# ICE.net
KiCad netlist of a schematic drawn in Altium Designer
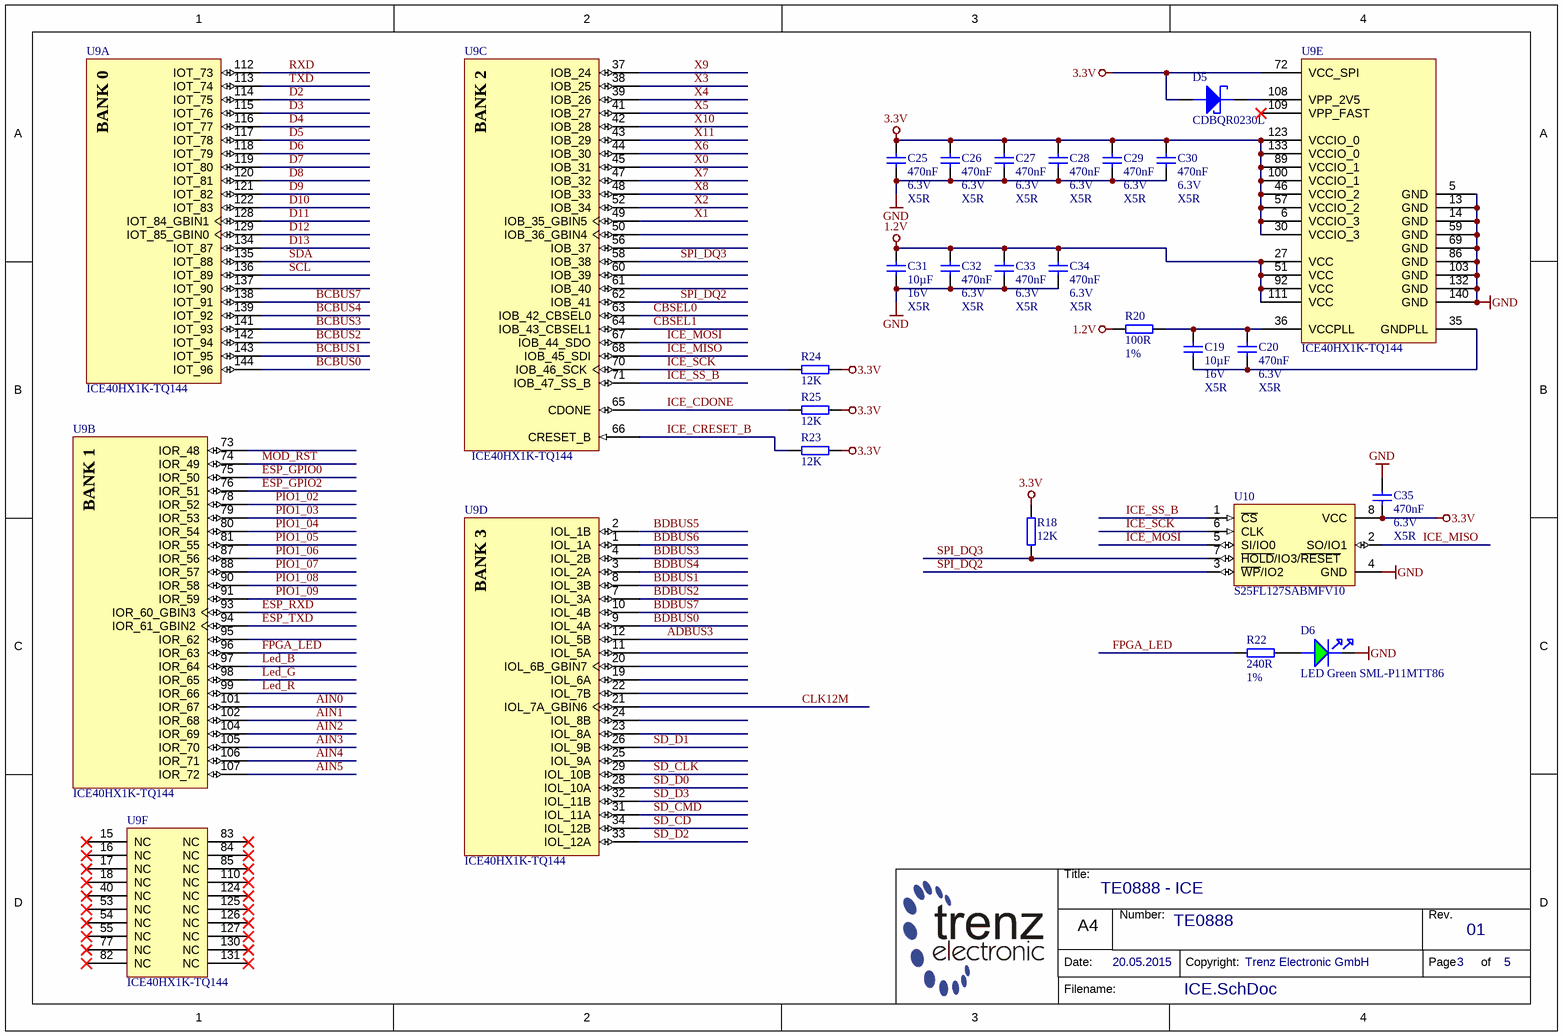
[diagram p0: ICE.SchDoc]

(export (version "E")
  (design (tool "Eeschema 10.0.6"))
  (components
    (comp (ref "C19")
      (value "10µF")
      (footprint "CAPC1608X90N")
      (description "KON 10µF 16V X5R SMD 20%")
      (fields
        (field (name "VOLTAGE") "16V")
        (field (name "TECHNOLOGY") "X5R")
        (field (name "TOLERANCE") "20%")
      )
      (libsource (lib "TE") (part "CAP-NP"))
    )
    (comp (ref "C20")
      (value "470nF")
      (footprint "CAPC0603X33N")
      (description "KON 470nF X5R 6.3V SMD 20%")
      (fields
        (field (name "VOLTAGE") "6.3V")
        (field (name "TECHNOLOGY") "X5R")
        (field (name "TOLERANCE") "20%")
      )
      (libsource (lib "TE") (part "CAP-NP"))
    )
    (comp (ref "C25")
      (value "470nF")
      (footprint "CAPC0603X33N")
      (description "KON 470nF X5R 6.3V SMD 20%")
      (fields
        (field (name "VOLTAGE") "6.3V")
        (field (name "TECHNOLOGY") "X5R")
        (field (name "TOLERANCE") "20%")
      )
      (libsource (lib "TE") (part "CAP-NP"))
    )
    (comp (ref "C26")
      (value "470nF")
      (footprint "CAPC0603X33N")
      (description "KON 470nF X5R 6.3V SMD 20%")
      (fields
        (field (name "VOLTAGE") "6.3V")
        (field (name "TECHNOLOGY") "X5R")
        (field (name "TOLERANCE") "20%")
      )
      (libsource (lib "TE") (part "CAP-NP"))
    )
    (comp (ref "C27")
      (value "470nF")
      (footprint "CAPC0603X33N")
      (description "KON 470nF X5R 6.3V SMD 20%")
      (fields
        (field (name "VOLTAGE") "6.3V")
        (field (name "TECHNOLOGY") "X5R")
        (field (name "TOLERANCE") "20%")
      )
      (libsource (lib "TE") (part "CAP-NP"))
    )
    (comp (ref "C28")
      (value "470nF")
      (footprint "CAPC0603X33N")
      (description "KON 470nF X5R 6.3V SMD 20%")
      (fields
        (field (name "VOLTAGE") "6.3V")
        (field (name "TECHNOLOGY") "X5R")
        (field (name "TOLERANCE") "20%")
      )
      (libsource (lib "TE") (part "CAP-NP"))
    )
    (comp (ref "C29")
      (value "470nF")
      (footprint "CAPC0603X33N")
      (description "KON 470nF X5R 6.3V SMD 20%")
      (fields
        (field (name "VOLTAGE") "6.3V")
        (field (name "TECHNOLOGY") "X5R")
        (field (name "TOLERANCE") "20%")
      )
      (libsource (lib "TE") (part "CAP-NP"))
    )
    (comp (ref "C30")
      (value "470nF")
      (footprint "CAPC0603X33N")
      (description "KON 470nF X5R 6.3V SMD 20%")
      (fields
        (field (name "VOLTAGE") "6.3V")
        (field (name "TECHNOLOGY") "X5R")
        (field (name "TOLERANCE") "20%")
      )
      (libsource (lib "TE") (part "CAP-NP"))
    )
    (comp (ref "C31")
      (value "10µF")
      (footprint "CAPC1608X90N")
      (description "KON 10µF 16V X5R SMD 20%")
      (fields
        (field (name "VOLTAGE") "16V")
        (field (name "TECHNOLOGY") "X5R")
        (field (name "TOLERANCE") "20%")
      )
      (libsource (lib "TE") (part "CAP-NP"))
    )
    (comp (ref "C32")
      (value "470nF")
      (footprint "CAPC0603X33N")
      (description "KON 470nF X5R 6.3V SMD 20%")
      (fields
        (field (name "VOLTAGE") "6.3V")
        (field (name "TECHNOLOGY") "X5R")
        (field (name "TOLERANCE") "20%")
      )
      (libsource (lib "TE") (part "CAP-NP"))
    )
    (comp (ref "C33")
      (value "470nF")
      (footprint "CAPC0603X33N")
      (description "KON 470nF X5R 6.3V SMD 20%")
      (fields
        (field (name "VOLTAGE") "6.3V")
        (field (name "TECHNOLOGY") "X5R")
        (field (name "TOLERANCE") "20%")
      )
      (libsource (lib "TE") (part "CAP-NP"))
    )
    (comp (ref "C34")
      (value "470nF")
      (footprint "CAPC0603X33N")
      (description "KON 470nF X5R 6.3V SMD 20%")
      (fields
        (field (name "VOLTAGE") "6.3V")
        (field (name "TECHNOLOGY") "X5R")
        (field (name "TOLERANCE") "20%")
      )
      (libsource (lib "TE") (part "CAP-NP"))
    )
    (comp (ref "C35")
      (value "470nF")
      (footprint "CAPC0603X33N")
      (description "KON 470nF X5R 6.3V SMD 20%")
      (fields
        (field (name "VOLTAGE") "6.3V")
        (field (name "TECHNOLOGY") "X5R")
        (field (name "TOLERANCE") "20%")
      )
      (libsource (lib "TE") (part "CAP-NP"))
    )
    (comp (ref "D5")
      (value "CDBQR0230L")
      (footprint "DIOC1006X55N")
      (fields (field (name "VOLTAGE") "0.2A"))
      (libsource (lib "TE") (part "SCHOTTKY"))
    )
    (comp (ref "D6")
      (value "LED Green SML-P11MTT86")
      (footprint "LEDC1006X25N_GREEN")
      (description "LED Grün SML-P11MTT86 SMD")
      (libsource (lib "TE") (part "LED_GRUEN"))
    )
    (comp (ref "R18")
      (value "12K")
      (footprint "RESC1005X40N")
      (description "WID SMD 12K 1% 0,063W")
      (libsource (lib "TE") (part "RES"))
    )
    (comp (ref "R20")
      (value "100R")
      (footprint "RESC1005X40N")
      (description "WID SMD 100R 1% 0,063W")
      (fields (field (name "TOLERANCE") "1%"))
      (libsource (lib "TE") (part "RES"))
    )
    (comp (ref "R22")
      (value "240R")
      (footprint "RESC1005X40N")
      (description "WID SMD 240R 1% 0,063W")
      (fields (field (name "TOLERANCE") "1%"))
      (libsource (lib "TE") (part "RES"))
    )
    (comp (ref "R23")
      (value "12K")
      (footprint "RESC1005X40N")
      (description "WID SMD 12K 1% 0,063W")
      (libsource (lib "TE") (part "RES"))
    )
    (comp (ref "R24")
      (value "12K")
      (footprint "RESC1005X40N")
      (description "WID SMD 12K 1% 0,063W")
      (libsource (lib "TE") (part "RES"))
    )
    (comp (ref "R25")
      (value "12K")
      (footprint "RESC1005X40N")
      (description "WID SMD 12K 1% 0,063W")
      (libsource (lib "TE") (part "RES"))
    )
    (comp (ref "U9")
      (value "ICE40HX1K-TQ144")
      (footprint "LATC-TQFP-144_N")
      (fields (field (name "MANUFACTURER") "Lattice Semiconductor"))
      (libsource (lib "Lattice iCE40") (part "ICE40HX1K-TQ144"))
    )
    (comp (ref "U10")
      (value "S25FL127SABMFV10")
      (footprint "SOIC127P790X216-8N")
      (description "S25FL127SABMFV10 automotive SO8")
      (libsource (lib "TE") (part "S25FL127S-SO8"))
    )
  )
  (nets
    (net (code "1") (name "/ADBUS3") (class "Default")
      (node (ref "U9") (pin "12") (pinfunction "IOL_5B_12") (pintype "bidirectional"))
    )
    (net (code "2") (name "/AIN0") (class "Default")
      (node (ref "U9") (pin "101") (pinfunction "IOR_67_101") (pintype "bidirectional"))
    )
    (net (code "3") (name "/AIN1") (class "Default")
      (node (ref "U9") (pin "102") (pinfunction "IOR_68_102") (pintype "bidirectional"))
    )
    (net (code "4") (name "/AIN2") (class "Default")
      (node (ref "U9") (pin "104") (pinfunction "IOR_69_104") (pintype "bidirectional"))
    )
    (net (code "5") (name "/AIN3") (class "Default")
      (node (ref "U9") (pin "105") (pinfunction "IOR_70_105") (pintype "bidirectional"))
    )
    (net (code "6") (name "/AIN4") (class "Default")
      (node (ref "U9") (pin "106") (pinfunction "IOR_71_106") (pintype "bidirectional"))
    )
    (net (code "7") (name "/AIN5") (class "Default")
      (node (ref "U9") (pin "107") (pinfunction "IOR_72_107") (pintype "bidirectional"))
    )
    (net (code "8") (name "/BCBUS0") (class "Default")
      (node (ref "U9") (pin "144") (pinfunction "IOT_96_144") (pintype "bidirectional"))
    )
    (net (code "9") (name "/BCBUS1") (class "Default")
      (node (ref "U9") (pin "143") (pinfunction "IOT_95_143") (pintype "bidirectional"))
    )
    (net (code "10") (name "/BCBUS2") (class "Default")
      (node (ref "U9") (pin "142") (pinfunction "IOT_94_142") (pintype "bidirectional"))
    )
    (net (code "11") (name "/BCBUS3") (class "Default")
      (node (ref "U9") (pin "141") (pinfunction "IOT_93_141") (pintype "bidirectional"))
    )
    (net (code "12") (name "/BCBUS4") (class "Default")
      (node (ref "U9") (pin "139") (pinfunction "IOT_92_139") (pintype "bidirectional"))
    )
    (net (code "13") (name "/BCBUS7") (class "Default")
      (node (ref "U9") (pin "138") (pinfunction "IOT_91_138") (pintype "bidirectional"))
    )
    (net (code "14") (name "/BDBUS0") (class "Default")
      (node (ref "U9") (pin "9") (pinfunction "IOL_4A_9") (pintype "bidirectional"))
    )
    (net (code "15") (name "/BDBUS1") (class "Default")
      (node (ref "U9") (pin "8") (pinfunction "IOL_3B_8") (pintype "bidirectional"))
    )
    (net (code "16") (name "/BDBUS2") (class "Default")
      (node (ref "U9") (pin "7") (pinfunction "IOL_3A_7") (pintype "bidirectional"))
    )
    (net (code "17") (name "/BDBUS3") (class "Default")
      (node (ref "U9") (pin "4") (pinfunction "IOL_2B_4") (pintype "bidirectional"))
    )
    (net (code "18") (name "/BDBUS4") (class "Default")
      (node (ref "U9") (pin "3") (pinfunction "IOL_2A_3") (pintype "bidirectional"))
    )
    (net (code "19") (name "/BDBUS5") (class "Default")
      (node (ref "U9") (pin "2") (pinfunction "IOL_1B_2") (pintype "bidirectional"))
    )
    (net (code "20") (name "/BDBUS6") (class "Default")
      (node (ref "U9") (pin "1") (pinfunction "IOL_1A_1") (pintype "bidirectional"))
    )
    (net (code "21") (name "/BDBUS7") (class "Default")
      (node (ref "U9") (pin "10") (pinfunction "IOL_4B_10") (pintype "bidirectional"))
    )
    (net (code "22") (name "/CBSEL0") (class "Default")
      (node (ref "U9") (pin "63") (pinfunction "IOB_42_CBSEL0_63") (pintype "bidirectional"))
    )
    (net (code "23") (name "/CBSEL1") (class "Default")
      (node (ref "U9") (pin "64") (pinfunction "IOB_43_CBSEL1_64") (pintype "bidirectional"))
    )
    (net (code "24") (name "/CLK12M") (class "Default")
      (node (ref "U9") (pin "21") (pinfunction "IOL_7A_GBIN6_21") (pintype "bidirectional"))
    )
    (net (code "25") (name "/D2") (class "Default")
      (node (ref "U9") (pin "114") (pinfunction "IOT_75_114") (pintype "bidirectional"))
    )
    (net (code "26") (name "/D3") (class "Default")
      (node (ref "U9") (pin "115") (pinfunction "IOT_76_115") (pintype "bidirectional"))
    )
    (net (code "27") (name "/D4") (class "Default")
      (node (ref "U9") (pin "116") (pinfunction "IOT_77_116") (pintype "bidirectional"))
    )
    (net (code "28") (name "/D5") (class "Default")
      (node (ref "U9") (pin "117") (pinfunction "IOT_78_117") (pintype "bidirectional"))
    )
    (net (code "29") (name "/D6") (class "Default")
      (node (ref "U9") (pin "118") (pinfunction "IOT_79_118") (pintype "bidirectional"))
    )
    (net (code "30") (name "/D7") (class "Default")
      (node (ref "U9") (pin "119") (pinfunction "IOT_80_119") (pintype "bidirectional"))
    )
    (net (code "31") (name "/D8") (class "Default")
      (node (ref "U9") (pin "120") (pinfunction "IOT_81_120") (pintype "bidirectional"))
    )
    (net (code "32") (name "/D9") (class "Default")
      (node (ref "U9") (pin "121") (pinfunction "IOT_82_121") (pintype "bidirectional"))
    )
    (net (code "33") (name "/D10") (class "Default")
      (node (ref "U9") (pin "122") (pinfunction "IOT_83_122") (pintype "bidirectional"))
    )
    (net (code "34") (name "/D11") (class "Default")
      (node (ref "U9") (pin "128") (pinfunction "IOT_84_GBIN1_128") (pintype "bidirectional"))
    )
    (net (code "35") (name "/D12") (class "Default")
      (node (ref "U9") (pin "129") (pinfunction "IOT_85_GBIN0_129") (pintype "bidirectional"))
    )
    (net (code "36") (name "/D13") (class "Default")
      (node (ref "U9") (pin "134") (pinfunction "IOT_87_134") (pintype "bidirectional"))
    )
    (net (code "37") (name "/ESP_GPIO0") (class "Default")
      (node (ref "U9") (pin "75") (pinfunction "IOR_50_75") (pintype "bidirectional"))
    )
    (net (code "38") (name "/ESP_GPIO2") (class "Default")
      (node (ref "U9") (pin "76") (pinfunction "IOR_51_76") (pintype "bidirectional"))
    )
    (net (code "39") (name "/ESP_RXD") (class "Default")
      (node (ref "U9") (pin "93") (pinfunction "IOR_60_GBIN3_93") (pintype "bidirectional"))
    )
    (net (code "40") (name "/ESP_TXD") (class "Default")
      (node (ref "U9") (pin "94") (pinfunction "IOR_61_GBIN2_94") (pintype "bidirectional"))
    )
    (net (code "41") (name "/FPGA_LED") (class "Default")
      (node (ref "R22") (pin "2") (pinfunction "2_2") (pintype "passive"))
      (node (ref "U9") (pin "96") (pinfunction "IOR_63_96") (pintype "bidirectional"))
    )
    (net (code "42") (name "/ICE_CDONE") (class "Default")
      (node (ref "R25") (pin "2") (pinfunction "2_2") (pintype "passive"))
      (node (ref "U9") (pin "65") (pinfunction "CDONE_65") (pintype "bidirectional"))
    )
    (net (code "43") (name "/ICE_CRESET_B") (class "Default")
      (node (ref "R23") (pin "2") (pinfunction "2_2") (pintype "passive"))
      (node (ref "U9") (pin "66") (pinfunction "CRESET_B_66") (pintype "input"))
    )
    (net (code "44") (name "/ICE_MISO") (class "Default")
      (node (ref "U10") (pin "2") (pinfunction "SO/IO1_2") (pintype "bidirectional"))
      (node (ref "U9") (pin "68") (pinfunction "IOB_45_SDI_68") (pintype "bidirectional"))
    )
    (net (code "45") (name "/ICE_MOSI") (class "Default")
      (node (ref "U10") (pin "5") (pinfunction "SI/IO0_5") (pintype "bidirectional"))
      (node (ref "U9") (pin "67") (pinfunction "IOB_44_SDO_67") (pintype "bidirectional"))
    )
    (net (code "46") (name "/ICE_SCK") (class "Default")
      (node (ref "R24") (pin "2") (pinfunction "2_2") (pintype "passive"))
      (node (ref "U10") (pin "6") (pinfunction "CLK_6") (pintype "input"))
      (node (ref "U9") (pin "70") (pinfunction "IOB_46_SCK_70") (pintype "bidirectional"))
    )
    (net (code "47") (name "/ICE_SS_B") (class "Default")
      (node (ref "U10") (pin "1") (pinfunction "~{CS}_1") (pintype "input"))
      (node (ref "U9") (pin "71") (pinfunction "IOB_47_SS_B_71") (pintype "bidirectional"))
    )
    (net (code "48") (name "/Led_B") (class "Default")
      (node (ref "U9") (pin "97") (pinfunction "IOR_64_97") (pintype "bidirectional"))
    )
    (net (code "49") (name "/Led_G") (class "Default")
      (node (ref "U9") (pin "98") (pinfunction "IOR_65_98") (pintype "bidirectional"))
    )
    (net (code "50") (name "/Led_R") (class "Default")
      (node (ref "U9") (pin "99") (pinfunction "IOR_66_99") (pintype "bidirectional"))
    )
    (net (code "51") (name "/MOD_RST") (class "Default")
      (node (ref "U9") (pin "74") (pinfunction "IOR_49_74") (pintype "bidirectional"))
    )
    (net (code "52") (name "/PIO1_02") (class "Default")
      (node (ref "U9") (pin "78") (pinfunction "IOR_52_78") (pintype "bidirectional"))
    )
    (net (code "53") (name "/PIO1_03") (class "Default")
      (node (ref "U9") (pin "79") (pinfunction "IOR_53_79") (pintype "bidirectional"))
    )
    (net (code "54") (name "/PIO1_04") (class "Default")
      (node (ref "U9") (pin "80") (pinfunction "IOR_54_80") (pintype "bidirectional"))
    )
    (net (code "55") (name "/PIO1_05") (class "Default")
      (node (ref "U9") (pin "81") (pinfunction "IOR_55_81") (pintype "bidirectional"))
    )
    (net (code "56") (name "/PIO1_06") (class "Default")
      (node (ref "U9") (pin "87") (pinfunction "IOR_56_87") (pintype "bidirectional"))
    )
    (net (code "57") (name "/PIO1_07") (class "Default")
      (node (ref "U9") (pin "88") (pinfunction "IOR_57_88") (pintype "bidirectional"))
    )
    (net (code "58") (name "/PIO1_08") (class "Default")
      (node (ref "U9") (pin "90") (pinfunction "IOR_58_90") (pintype "bidirectional"))
    )
    (net (code "59") (name "/PIO1_09") (class "Default")
      (node (ref "U9") (pin "91") (pinfunction "IOR_59_91") (pintype "bidirectional"))
    )
    (net (code "60") (name "/RXD") (class "Default")
      (node (ref "U9") (pin "112") (pinfunction "IOT_73_112") (pintype "bidirectional"))
    )
    (net (code "61") (name "/SCL") (class "Default")
      (node (ref "U9") (pin "136") (pinfunction "IOT_89_136") (pintype "bidirectional"))
    )
    (net (code "62") (name "/SDA") (class "Default")
      (node (ref "U9") (pin "135") (pinfunction "IOT_88_135") (pintype "bidirectional"))
    )
    (net (code "63") (name "/SD_CD") (class "Default")
      (node (ref "U9") (pin "34") (pinfunction "IOL_12B_34") (pintype "bidirectional"))
    )
    (net (code "64") (name "/SD_CLK") (class "Default")
      (node (ref "U9") (pin "29") (pinfunction "IOL_10B_29") (pintype "bidirectional"))
    )
    (net (code "65") (name "/SD_CMD") (class "Default")
      (node (ref "U9") (pin "31") (pinfunction "IOL_11A_31") (pintype "bidirectional"))
    )
    (net (code "66") (name "/SD_D0") (class "Default")
      (node (ref "U9") (pin "28") (pinfunction "IOL_10A_28") (pintype "bidirectional"))
    )
    (net (code "67") (name "/SD_D1") (class "Default")
      (node (ref "U9") (pin "26") (pinfunction "IOL_9B_26") (pintype "bidirectional"))
    )
    (net (code "68") (name "/SD_D2") (class "Default")
      (node (ref "U9") (pin "33") (pinfunction "IOL_12A_33") (pintype "bidirectional"))
    )
    (net (code "69") (name "/SD_D3") (class "Default")
      (node (ref "U9") (pin "32") (pinfunction "IOL_11B_32") (pintype "bidirectional"))
    )
    (net (code "70") (name "/SPI_DQ2") (class "Default")
      (node (ref "U10") (pin "3") (pinfunction "~{WP}/IO2_3") (pintype "bidirectional"))
      (node (ref "U9") (pin "62") (pinfunction "IOB_41_62") (pintype "bidirectional"))
    )
    (net (code "71") (name "/SPI_DQ3") (class "Default")
      (node (ref "R18") (pin "2") (pinfunction "2_2") (pintype "passive"))
      (node (ref "U10") (pin "7") (pinfunction "~{HOLD}/IO3/~{RESET}_7") (pintype "bidirectional"))
      (node (ref "U9") (pin "58") (pinfunction "IOB_38_58") (pintype "bidirectional"))
    )
    (net (code "72") (name "/TXD") (class "Default")
      (node (ref "U9") (pin "113") (pinfunction "IOT_74_113") (pintype "bidirectional"))
    )
    (net (code "73") (name "/X0") (class "Default")
      (node (ref "U9") (pin "45") (pinfunction "IOB_31_45") (pintype "bidirectional"))
    )
    (net (code "74") (name "/X1") (class "Default")
      (node (ref "U9") (pin "49") (pinfunction "IOB_35_GBIN5_49") (pintype "bidirectional"))
    )
    (net (code "75") (name "/X2") (class "Default")
      (node (ref "U9") (pin "52") (pinfunction "IOB_34_52") (pintype "bidirectional"))
    )
    (net (code "76") (name "/X3") (class "Default")
      (node (ref "U9") (pin "38") (pinfunction "IOB_25_38") (pintype "bidirectional"))
    )
    (net (code "77") (name "/X4") (class "Default")
      (node (ref "U9") (pin "39") (pinfunction "IOB_26_39") (pintype "bidirectional"))
    )
    (net (code "78") (name "/X5") (class "Default")
      (node (ref "U9") (pin "41") (pinfunction "IOB_27_41") (pintype "bidirectional"))
    )
    (net (code "79") (name "/X6") (class "Default")
      (node (ref "U9") (pin "44") (pinfunction "IOB_30_44") (pintype "bidirectional"))
    )
    (net (code "80") (name "/X7") (class "Default")
      (node (ref "U9") (pin "47") (pinfunction "IOB_32_47") (pintype "bidirectional"))
    )
    (net (code "81") (name "/X8") (class "Default")
      (node (ref "U9") (pin "48") (pinfunction "IOB_33_48") (pintype "bidirectional"))
    )
    (net (code "82") (name "/X9") (class "Default")
      (node (ref "U9") (pin "37") (pinfunction "IOB_24_37") (pintype "bidirectional"))
    )
    (net (code "83") (name "/X10") (class "Default")
      (node (ref "U9") (pin "42") (pinfunction "IOB_28_42") (pintype "bidirectional"))
    )
    (net (code "84") (name "/X11") (class "Default")
      (node (ref "U9") (pin "43") (pinfunction "IOB_29_43") (pintype "bidirectional"))
    )
    (net (code "85") (name "1.2V") (class "Default")
      (node (ref "C31") (pin "1") (pinfunction "1_1") (pintype "passive"))
      (node (ref "C32") (pin "2") (pinfunction "2_2") (pintype "passive"))
      (node (ref "C33") (pin "2") (pinfunction "2_2") (pintype "passive"))
      (node (ref "C34") (pin "2") (pinfunction "2_2") (pintype "passive"))
      (node (ref "R20") (pin "1") (pinfunction "1_1") (pintype "passive"))
      (node (ref "U9") (pin "111") (pinfunction "VCC_111") (pintype "power_in"))
      (node (ref "U9") (pin "27") (pinfunction "VCC_27") (pintype "power_in"))
      (node (ref "U9") (pin "51") (pinfunction "VCC_51") (pintype "power_in"))
      (node (ref "U9") (pin "92") (pinfunction "VCC_92") (pintype "power_in"))
    )
    (net (code "86") (name "3.3V") (class "Default")
      (node (ref "C25") (pin "2") (pinfunction "2_2") (pintype "passive"))
      (node (ref "C26") (pin "2") (pinfunction "2_2") (pintype "passive"))
      (node (ref "C27") (pin "2") (pinfunction "2_2") (pintype "passive"))
      (node (ref "C28") (pin "2") (pinfunction "2_2") (pintype "passive"))
      (node (ref "C29") (pin "2") (pinfunction "2_2") (pintype "passive"))
      (node (ref "C30") (pin "2") (pinfunction "2_2") (pintype "passive"))
      (node (ref "C35") (pin "1") (pinfunction "1_1") (pintype "passive"))
      (node (ref "D5") (pin "2") (pinfunction "ANODE_2") (pintype "passive"))
      (node (ref "R18") (pin "1") (pinfunction "1_1") (pintype "passive"))
      (node (ref "R23") (pin "1") (pinfunction "1_1") (pintype "passive"))
      (node (ref "R24") (pin "1") (pinfunction "1_1") (pintype "passive"))
      (node (ref "R25") (pin "1") (pinfunction "1_1") (pintype "passive"))
      (node (ref "U10") (pin "8") (pinfunction "VCC_8") (pintype "power_in"))
      (node (ref "U9") (pin "100") (pinfunction "VCCIO_1_100") (pintype "power_in"))
      (node (ref "U9") (pin "123") (pinfunction "VCCIO_0_123") (pintype "power_in"))
      (node (ref "U9") (pin "133") (pinfunction "VCCIO_0_133") (pintype "power_in"))
      (node (ref "U9") (pin "30") (pinfunction "VCCIO_3_30") (pintype "power_in"))
      (node (ref "U9") (pin "46") (pinfunction "VCCIO_2_46") (pintype "power_in"))
      (node (ref "U9") (pin "57") (pinfunction "VCCIO_2_57") (pintype "power_in"))
      (node (ref "U9") (pin "6") (pinfunction "VCCIO_3_6") (pintype "power_in"))
      (node (ref "U9") (pin "72") (pinfunction "VCC_SPI_72") (pintype "power_in"))
      (node (ref "U9") (pin "89") (pinfunction "VCCIO_1_89") (pintype "power_in"))
    )
    (net (code "87") (name "GND") (class "Default")
      (node (ref "C25") (pin "1") (pinfunction "1_1") (pintype "passive"))
      (node (ref "C26") (pin "1") (pinfunction "1_1") (pintype "passive"))
      (node (ref "C27") (pin "1") (pinfunction "1_1") (pintype "passive"))
      (node (ref "C28") (pin "1") (pinfunction "1_1") (pintype "passive"))
      (node (ref "C29") (pin "1") (pinfunction "1_1") (pintype "passive"))
      (node (ref "C30") (pin "1") (pinfunction "1_1") (pintype "passive"))
      (node (ref "C31") (pin "2") (pinfunction "2_2") (pintype "passive"))
      (node (ref "C32") (pin "1") (pinfunction "1_1") (pintype "passive"))
      (node (ref "C33") (pin "1") (pinfunction "1_1") (pintype "passive"))
      (node (ref "C34") (pin "1") (pinfunction "1_1") (pintype "passive"))
      (node (ref "C35") (pin "2") (pinfunction "2_2") (pintype "passive"))
      (node (ref "D6") (pin "K") (pinfunction "K_K") (pintype "passive"))
      (node (ref "U10") (pin "4") (pinfunction "GND_4") (pintype "power_in"))
      (node (ref "U9") (pin "103") (pinfunction "GND_103") (pintype "power_in"))
      (node (ref "U9") (pin "13") (pinfunction "GND_13") (pintype "power_in"))
      (node (ref "U9") (pin "132") (pinfunction "GND_132") (pintype "power_in"))
      (node (ref "U9") (pin "14") (pinfunction "GND_14") (pintype "power_in"))
      (node (ref "U9") (pin "140") (pinfunction "GND_140") (pintype "power_in"))
      (node (ref "U9") (pin "5") (pinfunction "GND_5") (pintype "power_in"))
      (node (ref "U9") (pin "59") (pinfunction "GND_59") (pintype "power_in"))
      (node (ref "U9") (pin "69") (pinfunction "GND_69") (pintype "power_in"))
      (node (ref "U9") (pin "86") (pinfunction "GND_86") (pintype "power_in"))
    )
    (net (code "88") (name "Net-(D5-KATHODE)") (class "Default")
      (node (ref "D5") (pin "1") (pinfunction "KATHODE_1") (pintype "passive"))
      (node (ref "U9") (pin "108") (pinfunction "VPP_2V5_108") (pintype "power_in"))
    )
    (net (code "89") (name "Net-(D6-PadA)") (class "Default")
      (node (ref "D6") (pin "A") (pinfunction "A_A") (pintype "passive"))
      (node (ref "R22") (pin "1") (pinfunction "1_1") (pintype "passive"))
    )
    (net (code "90") (name "Net-(U9E-GNDPLL)") (class "Default")
      (node (ref "C19") (pin "2") (pinfunction "2_2") (pintype "passive"))
      (node (ref "C20") (pin "1") (pinfunction "1_1") (pintype "passive"))
      (node (ref "U9") (pin "35") (pinfunction "GNDPLL_35") (pintype "power_in"))
    )
    (net (code "91") (name "Net-(U9E-VCCPLL)") (class "Default")
      (node (ref "C19") (pin "1") (pinfunction "1_1") (pintype "passive"))
      (node (ref "C20") (pin "2") (pinfunction "2_2") (pintype "passive"))
      (node (ref "R20") (pin "2") (pinfunction "2_2") (pintype "passive"))
      (node (ref "U9") (pin "36") (pinfunction "VCCPLL_36") (pintype "power_in"))
    )
    (net (code "92") (name "unconnected-(U9A-IOT_90-Pad137)") (class "Default")
      (node (ref "U9") (pin "137") (pinfunction "IOT_90_137") (pintype "bidirectional"))
    )
    (net (code "93") (name "unconnected-(U9B-IOR_48-Pad73)") (class "Default")
      (node (ref "U9") (pin "73") (pinfunction "IOR_48_73") (pintype "bidirectional"))
    )
    (net (code "94") (name "unconnected-(U9B-IOR_62-Pad95)") (class "Default")
      (node (ref "U9") (pin "95") (pinfunction "IOR_62_95") (pintype "bidirectional"))
    )
    (net (code "95") (name "unconnected-(U9C-IOB_36_GBIN4-Pad50)") (class "Default")
      (node (ref "U9") (pin "50") (pinfunction "IOB_36_GBIN4_50") (pintype "bidirectional"))
    )
    (net (code "96") (name "unconnected-(U9C-IOB_37-Pad56)") (class "Default")
      (node (ref "U9") (pin "56") (pinfunction "IOB_37_56") (pintype "bidirectional"))
    )
    (net (code "97") (name "unconnected-(U9C-IOB_39-Pad60)") (class "Default")
      (node (ref "U9") (pin "60") (pinfunction "IOB_39_60") (pintype "bidirectional"))
    )
    (net (code "98") (name "unconnected-(U9C-IOB_40-Pad61)") (class "Default")
      (node (ref "U9") (pin "61") (pinfunction "IOB_40_61") (pintype "bidirectional"))
    )
    (net (code "99") (name "unconnected-(U9D-IOL_5A-Pad11)") (class "Default")
      (node (ref "U9") (pin "11") (pinfunction "IOL_5A_11") (pintype "bidirectional"))
    )
    (net (code "100") (name "unconnected-(U9D-IOL_6A-Pad19)") (class "Default")
      (node (ref "U9") (pin "19") (pinfunction "IOL_6A_19") (pintype "bidirectional"))
    )
    (net (code "101") (name "unconnected-(U9D-IOL_6B_GBIN7-Pad20)") (class "Default")
      (node (ref "U9") (pin "20") (pinfunction "IOL_6B_GBIN7_20") (pintype "bidirectional"))
    )
    (net (code "102") (name "unconnected-(U9D-IOL_7B-Pad22)") (class "Default")
      (node (ref "U9") (pin "22") (pinfunction "IOL_7B_22") (pintype "bidirectional"))
    )
    (net (code "103") (name "unconnected-(U9D-IOL_8A-Pad23)") (class "Default")
      (node (ref "U9") (pin "23") (pinfunction "IOL_8A_23") (pintype "bidirectional"))
    )
    (net (code "104") (name "unconnected-(U9D-IOL_8B-Pad24)") (class "Default")
      (node (ref "U9") (pin "24") (pinfunction "IOL_8B_24") (pintype "bidirectional"))
    )
    (net (code "105") (name "unconnected-(U9D-IOL_9A-Pad25)") (class "Default")
      (node (ref "U9") (pin "25") (pinfunction "IOL_9A_25") (pintype "bidirectional"))
    )
    (net (code "106") (name "unconnected-(U9E-VPP_FAST-Pad109)") (class "Default")
      (node (ref "U9") (pin "109") (pinfunction "VPP_FAST_109") (pintype "power_in+no_connect"))
    )
    (net (code "107") (name "unconnected-(U9F-NC-Pad15)") (class "Default")
      (node (ref "U9") (pin "15") (pinfunction "NC_15") (pintype "passive+no_connect"))
    )
    (net (code "108") (name "unconnected-(U9F-NC-Pad16)") (class "Default")
      (node (ref "U9") (pin "16") (pinfunction "NC_16") (pintype "passive+no_connect"))
    )
    (net (code "109") (name "unconnected-(U9F-NC-Pad17)") (class "Default")
      (node (ref "U9") (pin "17") (pinfunction "NC_17") (pintype "passive+no_connect"))
    )
    (net (code "110") (name "unconnected-(U9F-NC-Pad18)") (class "Default")
      (node (ref "U9") (pin "18") (pinfunction "NC_18") (pintype "passive+no_connect"))
    )
    (net (code "111") (name "unconnected-(U9F-NC-Pad40)") (class "Default")
      (node (ref "U9") (pin "40") (pinfunction "NC_40") (pintype "passive+no_connect"))
    )
    (net (code "112") (name "unconnected-(U9F-NC-Pad53)") (class "Default")
      (node (ref "U9") (pin "53") (pinfunction "NC_53") (pintype "passive+no_connect"))
    )
    (net (code "113") (name "unconnected-(U9F-NC-Pad54)") (class "Default")
      (node (ref "U9") (pin "54") (pinfunction "NC_54") (pintype "passive+no_connect"))
    )
    (net (code "114") (name "unconnected-(U9F-NC-Pad55)") (class "Default")
      (node (ref "U9") (pin "55") (pinfunction "NC_55") (pintype "passive+no_connect"))
    )
    (net (code "115") (name "unconnected-(U9F-NC-Pad77)") (class "Default")
      (node (ref "U9") (pin "77") (pinfunction "NC_77") (pintype "passive+no_connect"))
    )
    (net (code "116") (name "unconnected-(U9F-NC-Pad82)") (class "Default")
      (node (ref "U9") (pin "82") (pinfunction "NC_82") (pintype "passive+no_connect"))
    )
    (net (code "117") (name "unconnected-(U9F-NC-Pad83)") (class "Default")
      (node (ref "U9") (pin "83") (pinfunction "NC_83") (pintype "passive+no_connect"))
    )
    (net (code "118") (name "unconnected-(U9F-NC-Pad84)") (class "Default")
      (node (ref "U9") (pin "84") (pinfunction "NC_84") (pintype "passive+no_connect"))
    )
    (net (code "119") (name "unconnected-(U9F-NC-Pad85)") (class "Default")
      (node (ref "U9") (pin "85") (pinfunction "NC_85") (pintype "passive+no_connect"))
    )
    (net (code "120") (name "unconnected-(U9F-NC-Pad110)") (class "Default")
      (node (ref "U9") (pin "110") (pinfunction "NC_110") (pintype "passive+no_connect"))
    )
    (net (code "121") (name "unconnected-(U9F-NC-Pad124)") (class "Default")
      (node (ref "U9") (pin "124") (pinfunction "NC_124") (pintype "passive+no_connect"))
    )
    (net (code "122") (name "unconnected-(U9F-NC-Pad125)") (class "Default")
      (node (ref "U9") (pin "125") (pinfunction "NC_125") (pintype "passive+no_connect"))
    )
    (net (code "123") (name "unconnected-(U9F-NC-Pad126)") (class "Default")
      (node (ref "U9") (pin "126") (pinfunction "NC_126") (pintype "passive+no_connect"))
    )
    (net (code "124") (name "unconnected-(U9F-NC-Pad127)") (class "Default")
      (node (ref "U9") (pin "127") (pinfunction "NC_127") (pintype "passive+no_connect"))
    )
    (net (code "125") (name "unconnected-(U9F-NC-Pad130)") (class "Default")
      (node (ref "U9") (pin "130") (pinfunction "NC_130") (pintype "passive+no_connect"))
    )
    (net (code "126") (name "unconnected-(U9F-NC-Pad131)") (class "Default")
      (node (ref "U9") (pin "131") (pinfunction "NC_131") (pintype "passive+no_connect"))
    )
  )
)
